# MirOculousShieldv2.net
KiCad netlist of a schematic drawn in EAGLE
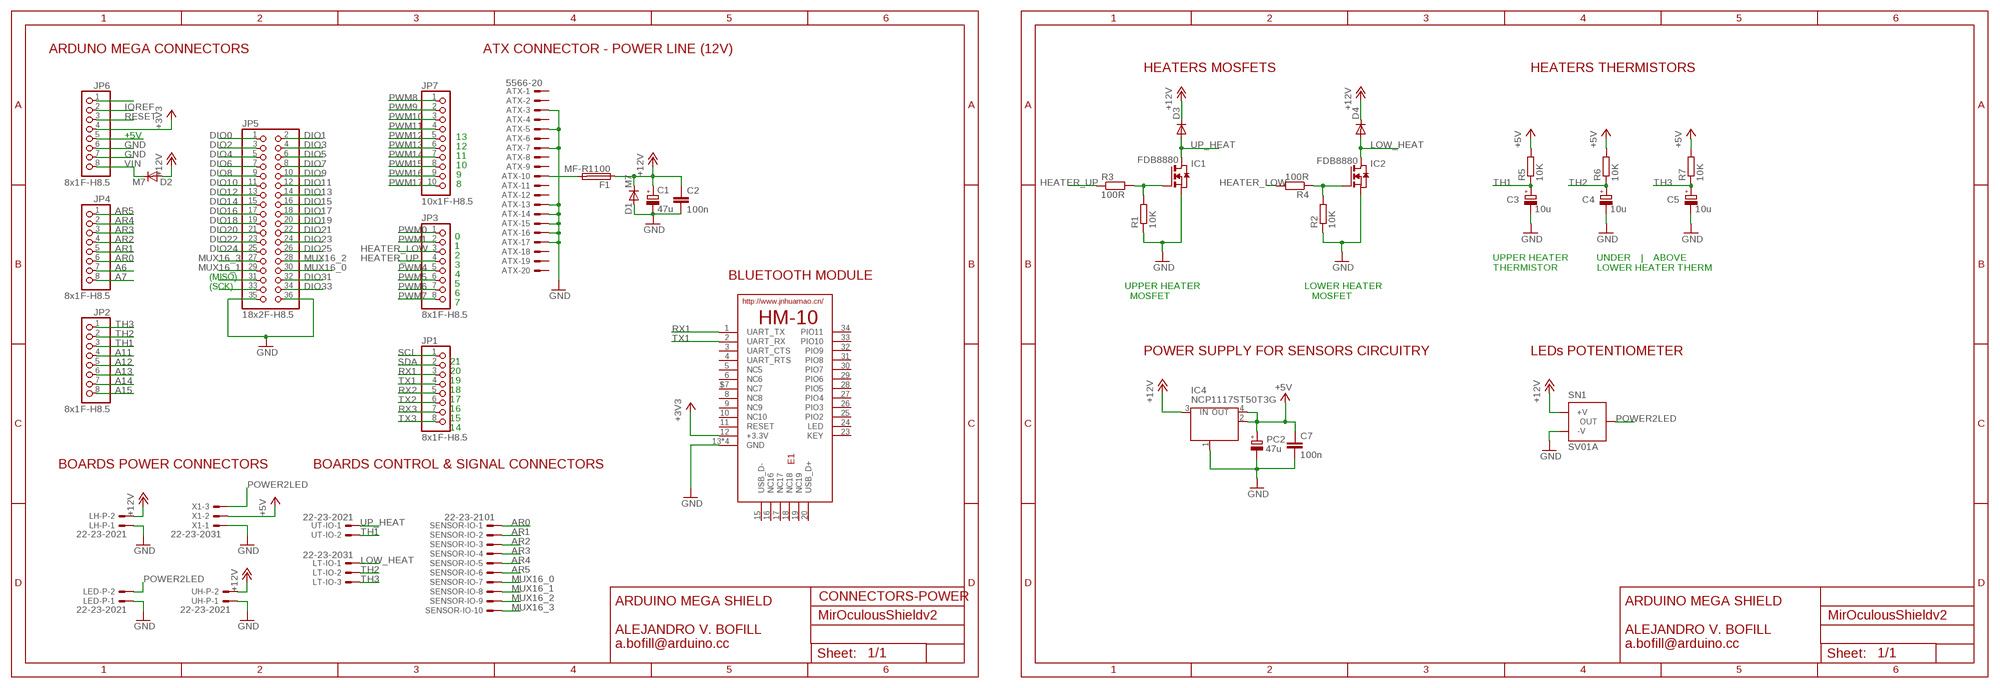
[diagram p0: schematic, sheet 1]

(export (version "E")
  (design (tool "Eeschema 10.0.6"))
  (components
    (comp (ref "ATX")
      (value "5566-20")
      (footprint "eagle-import:5566-20")
      (fields (field (name "OC_FARNELL") "9734252"))
      (libsource (lib "eagle-import") (part "5566-20"))
    )
    (comp (ref "C1")
      (value "47u")
      (footprint "eagle-import:PANASONIC_D")
      (libsource (lib "eagle-import") (part "CPOL-EUD"))
    )
    (comp (ref "C2")
      (value "100n")
      (footprint "eagle-import:C0603")
      (libsource (lib "eagle-import") (part "C-EUC0603"))
    )
    (comp (ref "C3")
      (value "10u")
      (footprint "eagle-import:A_3216-18R")
      (libsource (lib "eagle-import") (part "CPOL-EUA/3216-18R"))
    )
    (comp (ref "C4")
      (value "10u")
      (footprint "eagle-import:A_3216-18R")
      (libsource (lib "eagle-import") (part "CPOL-EUA/3216-18R"))
    )
    (comp (ref "C5")
      (value "10u")
      (footprint "eagle-import:A_3216-18R")
      (libsource (lib "eagle-import") (part "CPOL-EUA/3216-18R"))
    )
    (comp (ref "C7")
      (value "100n")
      (footprint "eagle-import:C0603")
      (libsource (lib "eagle-import") (part "C-EUC0603"))
    )
    (comp (ref "D1")
      (value "M7")
      (footprint "eagle-import:SMB")
      (libsource (lib "eagle-import") (part "DIODE-SMB"))
    )
    (comp (ref "D2")
      (value "M7")
      (footprint "eagle-import:SMB")
      (libsource (lib "eagle-import") (part "DIODE-SMB"))
    )
    (comp (ref "D3")
      (value "RGL34A")
      (footprint "eagle-import:DO-213AA_DIODE")
      (libsource (lib "eagle-import") (part "DO-213_DIODE"))
    )
    (comp (ref "D4")
      (value "RGL34A")
      (footprint "eagle-import:DO-213AA_DIODE")
      (libsource (lib "eagle-import") (part "DO-213_DIODE"))
    )
    (comp (ref "E1")
      (value "HM-10-BOARD")
      (footprint "eagle-import:26.9X13X2.2_BOARD")
      (libsource (lib "eagle-import") (part "HM-10-BOARD"))
    )
    (comp (ref "F1")
      (value "MF-R1100")
      (footprint "eagle-import:LITTLEFUSE")
      (libsource (lib "eagle-import") (part "LITTLEFUSE"))
    )
    (comp (ref "IC1")
      (value "FDB8880")
      (footprint "eagle-import:FDB8880")
      (libsource (lib "eagle-import") (part "FDB8880"))
    )
    (comp (ref "IC2")
      (value "FDB8880")
      (footprint "eagle-import:FDB8880")
      (libsource (lib "eagle-import") (part "FDB8880"))
    )
    (comp (ref "IC4")
      (value "NCP1117ST50T3G")
      (footprint "eagle-import:SOT223")
      (libsource (lib "eagle-import") (part "MC33269ST-3.3T3"))
    )
    (comp (ref "JP1")
      (value "8x1F-H8.5")
      (footprint "eagle-import:1X08")
      (libsource (lib "eagle-import") (part "PINHD-1X8"))
    )
    (comp (ref "JP2")
      (value "8x1F-H8.5")
      (footprint "eagle-import:1X08")
      (libsource (lib "eagle-import") (part "PINHD-1X8"))
    )
    (comp (ref "JP3")
      (value "8x1F-H8.5")
      (footprint "eagle-import:1X08")
      (libsource (lib "eagle-import") (part "PINHD-1X8"))
    )
    (comp (ref "JP4")
      (value "8x1F-H8.5")
      (footprint "eagle-import:1X08")
      (libsource (lib "eagle-import") (part "PINHD-1X8"))
    )
    (comp (ref "JP5")
      (value "18x2F-H8.5")
      (footprint "eagle-import:2X18")
      (libsource (lib "eagle-import") (part "PINHD-2X18"))
    )
    (comp (ref "JP6")
      (value "8x1F-H8.5")
      (footprint "eagle-import:1X08")
      (libsource (lib "eagle-import") (part "PINHD-1X8"))
    )
    (comp (ref "JP7")
      (value "10x1F-H8.5")
      (footprint "eagle-import:1X10")
      (libsource (lib "eagle-import") (part "PINHD-1X10_ARD"))
    )
    (comp (ref "LED-P")
      (value "22-23-2021")
      (footprint "eagle-import:22-23-2021")
      (fields (field (name "MF") "MOLEX"))
      (libsource (lib "eagle-import") (part "22-23-2021"))
    )
    (comp (ref "LH-P")
      (value "22-23-2021")
      (footprint "eagle-import:22-23-2021")
      (fields (field (name "MF") "MOLEX"))
      (libsource (lib "eagle-import") (part "22-23-2021"))
    )
    (comp (ref "LT-IO")
      (value "22-23-2031")
      (footprint "eagle-import:22-23-2031")
      (fields (field (name "MF") "MOLEX"))
      (libsource (lib "eagle-import") (part "22-23-2031"))
    )
    (comp (ref "PC2")
      (value "47u")
      (footprint "eagle-import:PANASONIC_D")
      (libsource (lib "eagle-import") (part "CPOL-EUD"))
    )
    (comp (ref "R1")
      (value "10K")
      (footprint "eagle-import:R0603")
      (libsource (lib "eagle-import") (part "R-EU_R0603"))
    )
    (comp (ref "R2")
      (value "10K")
      (footprint "eagle-import:R0603")
      (libsource (lib "eagle-import") (part "R-EU_R0603"))
    )
    (comp (ref "R3")
      (value "100R")
      (footprint "eagle-import:R0603")
      (libsource (lib "eagle-import") (part "R-EU_R0603"))
    )
    (comp (ref "R4")
      (value "100R")
      (footprint "eagle-import:R0603")
      (libsource (lib "eagle-import") (part "R-EU_R0603"))
    )
    (comp (ref "R5")
      (value "10K")
      (footprint "eagle-import:R0603")
      (libsource (lib "eagle-import") (part "R-EU_R0603"))
    )
    (comp (ref "R6")
      (value "10K")
      (footprint "eagle-import:R0603")
      (libsource (lib "eagle-import") (part "R-EU_R0603"))
    )
    (comp (ref "R7")
      (value "10K")
      (footprint "eagle-import:R0603")
      (libsource (lib "eagle-import") (part "R-EU_R0603"))
    )
    (comp (ref "SENSOR-IO")
      (value "22-23-2101")
      (footprint "eagle-import:22-23-2101")
      (fields (field (name "MF") "MOLEX"))
      (libsource (lib "eagle-import") (part "22-23-2101"))
    )
    (comp (ref "SN1")
      (value "SV01A")
      (footprint "eagle-import:SV01A")
      (libsource (lib "eagle-import") (part "SV01A"))
    )
    (comp (ref "UH-P")
      (value "22-23-2021")
      (footprint "eagle-import:22-23-2021")
      (fields (field (name "MF") "MOLEX"))
      (libsource (lib "eagle-import") (part "22-23-2021"))
    )
    (comp (ref "UT-IO")
      (value "22-23-2021")
      (footprint "eagle-import:22-23-2021")
      (fields (field (name "MF") "MOLEX"))
      (libsource (lib "eagle-import") (part "22-23-2021"))
    )
    (comp (ref "X1")
      (value "22-23-2031")
      (footprint "eagle-import:22-23-2031")
      (fields (field (name "MF") "MOLEX"))
      (libsource (lib "eagle-import") (part "22-23-2031"))
    )
  )
  (nets
    (net (code "1") (name "+3V3") (class "Default")
      (node (ref "E1") (pin "12") (pinfunction "+3.3V_12") (pintype "bidirectional"))
      (node (ref "JP6") (pin "4") (pinfunction "4_4") (pintype "passive"))
    )
    (net (code "2") (name "+5V") (class "Default")
      (node (ref "C7") (pin "1") (pinfunction "1_1") (pintype "passive"))
      (node (ref "IC4") (pin "2") (pinfunction "OUT_2") (pintype "passive"))
      (node (ref "IC4") (pin "4") (pinfunction "OUT_4") (pintype "passive"))
      (node (ref "PC2") (pin "+") (pinfunction "+_+") (pintype "passive"))
      (node (ref "R5") (pin "2") (pinfunction "2_2") (pintype "passive"))
      (node (ref "R6") (pin "2") (pinfunction "2_2") (pintype "passive"))
      (node (ref "R7") (pin "2") (pinfunction "2_2") (pintype "passive"))
      (node (ref "X1") (pin "2") (pinfunction "S_2") (pintype "passive"))
    )
    (net (code "3") (name "+12V") (class "Default")
      (node (ref "C1") (pin "+") (pinfunction "+_+") (pintype "passive"))
      (node (ref "C2") (pin "1") (pinfunction "1_1") (pintype "passive"))
      (node (ref "D1") (pin "C") (pinfunction "C_C") (pintype "passive"))
      (node (ref "D2") (pin "A") (pinfunction "A_A") (pintype "passive"))
      (node (ref "D3") (pin "P$2") (pinfunction "C_P$2") (pintype "passive"))
      (node (ref "D4") (pin "P$2") (pinfunction "C_P$2") (pintype "passive"))
      (node (ref "F1") (pin "1") (pinfunction "1_1") (pintype "passive"))
      (node (ref "IC4") (pin "3") (pinfunction "IN_3") (pintype "input"))
      (node (ref "LH-P") (pin "2") (pinfunction "S_2") (pintype "passive"))
      (node (ref "SN1") (pin "3") (pinfunction "+V_3") (pintype "passive"))
      (node (ref "UH-P") (pin "2") (pinfunction "S_2") (pintype "passive"))
    )
    (net (code "4") (name "/A6") (class "Default")
      (node (ref "JP4") (pin "7") (pinfunction "7_7") (pintype "passive"))
    )
    (net (code "5") (name "/A7") (class "Default")
      (node (ref "JP4") (pin "8") (pinfunction "8_8") (pintype "passive"))
    )
    (net (code "6") (name "/A11") (class "Default")
      (node (ref "JP2") (pin "4") (pinfunction "4_4") (pintype "passive"))
    )
    (net (code "7") (name "/A12") (class "Default")
      (node (ref "JP2") (pin "5") (pinfunction "5_5") (pintype "passive"))
    )
    (net (code "8") (name "/A13") (class "Default")
      (node (ref "JP2") (pin "6") (pinfunction "6_6") (pintype "passive"))
    )
    (net (code "9") (name "/A14") (class "Default")
      (node (ref "JP2") (pin "7") (pinfunction "7_7") (pintype "passive"))
    )
    (net (code "10") (name "/A15") (class "Default")
      (node (ref "JP2") (pin "8") (pinfunction "8_8") (pintype "passive"))
    )
    (net (code "11") (name "/AR0") (class "Default")
      (node (ref "JP4") (pin "6") (pinfunction "6_6") (pintype "passive"))
      (node (ref "SENSOR-IO") (pin "1") (pinfunction "S_1") (pintype "passive"))
    )
    (net (code "12") (name "/AR1") (class "Default")
      (node (ref "JP4") (pin "5") (pinfunction "5_5") (pintype "passive"))
      (node (ref "SENSOR-IO") (pin "2") (pinfunction "S_2") (pintype "passive"))
    )
    (net (code "13") (name "/AR2") (class "Default")
      (node (ref "JP4") (pin "4") (pinfunction "4_4") (pintype "passive"))
      (node (ref "SENSOR-IO") (pin "3") (pinfunction "S_3") (pintype "passive"))
    )
    (net (code "14") (name "/AR3") (class "Default")
      (node (ref "JP4") (pin "3") (pinfunction "3_3") (pintype "passive"))
      (node (ref "SENSOR-IO") (pin "4") (pinfunction "S_4") (pintype "passive"))
    )
    (net (code "15") (name "/AR4") (class "Default")
      (node (ref "JP4") (pin "2") (pinfunction "2_2") (pintype "passive"))
      (node (ref "SENSOR-IO") (pin "5") (pinfunction "S_5") (pintype "passive"))
    )
    (net (code "16") (name "/AR5") (class "Default")
      (node (ref "JP4") (pin "1") (pinfunction "1_1") (pintype "passive"))
      (node (ref "SENSOR-IO") (pin "6") (pinfunction "S_6") (pintype "passive"))
    )
    (net (code "17") (name "/DIO0") (class "Default")
      (node (ref "JP5") (pin "1") (pinfunction "1_1") (pintype "passive"))
    )
    (net (code "18") (name "/DIO1") (class "Default")
      (node (ref "JP5") (pin "2") (pinfunction "2_2") (pintype "passive"))
    )
    (net (code "19") (name "/DIO2") (class "Default")
      (node (ref "JP5") (pin "3") (pinfunction "3_3") (pintype "passive"))
    )
    (net (code "20") (name "/DIO3") (class "Default")
      (node (ref "JP5") (pin "4") (pinfunction "4_4") (pintype "passive"))
    )
    (net (code "21") (name "/DIO4") (class "Default")
      (node (ref "JP5") (pin "5") (pinfunction "5_5") (pintype "passive"))
    )
    (net (code "22") (name "/DIO5") (class "Default")
      (node (ref "JP5") (pin "6") (pinfunction "6_6") (pintype "passive"))
    )
    (net (code "23") (name "/DIO6") (class "Default")
      (node (ref "JP5") (pin "7") (pinfunction "7_7") (pintype "passive"))
    )
    (net (code "24") (name "/DIO7") (class "Default")
      (node (ref "JP5") (pin "8") (pinfunction "8_8") (pintype "passive"))
    )
    (net (code "25") (name "/DIO8") (class "Default")
      (node (ref "JP5") (pin "9") (pinfunction "9_9") (pintype "passive"))
    )
    (net (code "26") (name "/DIO9") (class "Default")
      (node (ref "JP5") (pin "10") (pinfunction "10_10") (pintype "passive"))
    )
    (net (code "27") (name "/DIO10") (class "Default")
      (node (ref "JP5") (pin "11") (pinfunction "11_11") (pintype "passive"))
    )
    (net (code "28") (name "/DIO11") (class "Default")
      (node (ref "JP5") (pin "12") (pinfunction "12_12") (pintype "passive"))
    )
    (net (code "29") (name "/DIO12") (class "Default")
      (node (ref "JP5") (pin "13") (pinfunction "13_13") (pintype "passive"))
    )
    (net (code "30") (name "/DIO13") (class "Default")
      (node (ref "JP5") (pin "14") (pinfunction "14_14") (pintype "passive"))
    )
    (net (code "31") (name "/DIO14") (class "Default")
      (node (ref "JP5") (pin "15") (pinfunction "15_15") (pintype "passive"))
    )
    (net (code "32") (name "/DIO15") (class "Default")
      (node (ref "JP5") (pin "16") (pinfunction "16_16") (pintype "passive"))
    )
    (net (code "33") (name "/DIO16") (class "Default")
      (node (ref "JP5") (pin "17") (pinfunction "17_17") (pintype "passive"))
    )
    (net (code "34") (name "/DIO17") (class "Default")
      (node (ref "JP5") (pin "18") (pinfunction "18_18") (pintype "passive"))
    )
    (net (code "35") (name "/DIO18") (class "Default")
      (node (ref "JP5") (pin "19") (pinfunction "19_19") (pintype "passive"))
    )
    (net (code "36") (name "/DIO19") (class "Default")
      (node (ref "JP5") (pin "20") (pinfunction "20_20") (pintype "passive"))
    )
    (net (code "37") (name "/DIO20") (class "Default")
      (node (ref "JP5") (pin "21") (pinfunction "21_21") (pintype "passive"))
    )
    (net (code "38") (name "/DIO21") (class "Default")
      (node (ref "JP5") (pin "22") (pinfunction "22_22") (pintype "passive"))
    )
    (net (code "39") (name "/DIO22") (class "Default")
      (node (ref "JP5") (pin "23") (pinfunction "23_23") (pintype "passive"))
    )
    (net (code "40") (name "/DIO23") (class "Default")
      (node (ref "JP5") (pin "24") (pinfunction "24_24") (pintype "passive"))
    )
    (net (code "41") (name "/DIO24") (class "Default")
      (node (ref "JP5") (pin "25") (pinfunction "25_25") (pintype "passive"))
    )
    (net (code "42") (name "/DIO25") (class "Default")
      (node (ref "JP5") (pin "26") (pinfunction "26_26") (pintype "passive"))
    )
    (net (code "43") (name "/DIO31") (class "Default")
      (node (ref "JP5") (pin "32") (pinfunction "32_32") (pintype "passive"))
    )
    (net (code "44") (name "/DIO33") (class "Default")
      (node (ref "JP5") (pin "34") (pinfunction "34_34") (pintype "passive"))
    )
    (net (code "45") (name "/HEATER_LOW") (class "Default")
      (node (ref "JP3") (pin "3") (pinfunction "3_3") (pintype "passive"))
      (node (ref "R4") (pin "2") (pinfunction "2_2") (pintype "passive"))
    )
    (net (code "46") (name "/HEATER_UP") (class "Default")
      (node (ref "JP3") (pin "4") (pinfunction "4_4") (pintype "passive"))
      (node (ref "R3") (pin "1") (pinfunction "1_1") (pintype "passive"))
    )
    (net (code "47") (name "/IOREF") (class "Default")
      (node (ref "JP6") (pin "2") (pinfunction "2_2") (pintype "passive"))
    )
    (net (code "48") (name "/LOW_HEAT") (class "Default")
      (node (ref "D4") (pin "P$1") (pinfunction "A_P$1") (pintype "passive"))
      (node (ref "IC2") (pin "2") (pinfunction "D_2") (pintype "passive"))
      (node (ref "LT-IO") (pin "1") (pinfunction "S_1") (pintype "passive"))
    )
    (net (code "49") (name "/MUX16_0") (class "Default")
      (node (ref "JP5") (pin "30") (pinfunction "30_30") (pintype "passive"))
      (node (ref "SENSOR-IO") (pin "7") (pinfunction "S_7") (pintype "passive"))
    )
    (net (code "50") (name "/MUX16_1") (class "Default")
      (node (ref "JP5") (pin "29") (pinfunction "29_29") (pintype "passive"))
      (node (ref "SENSOR-IO") (pin "8") (pinfunction "S_8") (pintype "passive"))
    )
    (net (code "51") (name "/MUX16_2") (class "Default")
      (node (ref "JP5") (pin "28") (pinfunction "28_28") (pintype "passive"))
      (node (ref "SENSOR-IO") (pin "9") (pinfunction "S_9") (pintype "passive"))
    )
    (net (code "52") (name "/MUX16_3") (class "Default")
      (node (ref "JP5") (pin "27") (pinfunction "27_27") (pintype "passive"))
      (node (ref "SENSOR-IO") (pin "10") (pinfunction "S_10") (pintype "passive"))
    )
    (net (code "53") (name "/POWER2LED") (class "Default")
      (node (ref "LED-P") (pin "2") (pinfunction "S_2") (pintype "passive"))
      (node (ref "SN1") (pin "2") (pinfunction "OUT_2") (pintype "passive"))
      (node (ref "X1") (pin "3") (pinfunction "S_3") (pintype "passive"))
    )
    (net (code "54") (name "/PWM0") (class "Default")
      (node (ref "JP3") (pin "1") (pinfunction "1_1") (pintype "passive"))
    )
    (net (code "55") (name "/PWM1") (class "Default")
      (node (ref "JP3") (pin "2") (pinfunction "2_2") (pintype "passive"))
    )
    (net (code "56") (name "/PWM4") (class "Default")
      (node (ref "JP3") (pin "5") (pinfunction "5_5") (pintype "passive"))
    )
    (net (code "57") (name "/PWM5") (class "Default")
      (node (ref "JP3") (pin "6") (pinfunction "6_6") (pintype "passive"))
    )
    (net (code "58") (name "/PWM6") (class "Default")
      (node (ref "JP3") (pin "7") (pinfunction "7_7") (pintype "passive"))
    )
    (net (code "59") (name "/PWM7") (class "Default")
      (node (ref "JP3") (pin "8") (pinfunction "8_8") (pintype "passive"))
    )
    (net (code "60") (name "/PWM8") (class "Default")
      (node (ref "JP7") (pin "1") (pinfunction "1_1") (pintype "passive"))
    )
    (net (code "61") (name "/PWM9") (class "Default")
      (node (ref "JP7") (pin "2") (pinfunction "2_2") (pintype "passive"))
    )
    (net (code "62") (name "/PWM10") (class "Default")
      (node (ref "JP7") (pin "3") (pinfunction "3_3") (pintype "passive"))
    )
    (net (code "63") (name "/PWM11") (class "Default")
      (node (ref "JP7") (pin "4") (pinfunction "4_4") (pintype "passive"))
    )
    (net (code "64") (name "/PWM12") (class "Default")
      (node (ref "JP7") (pin "5") (pinfunction "5_5") (pintype "passive"))
    )
    (net (code "65") (name "/PWM13") (class "Default")
      (node (ref "JP7") (pin "6") (pinfunction "6_6") (pintype "passive"))
    )
    (net (code "66") (name "/PWM14") (class "Default")
      (node (ref "JP7") (pin "7") (pinfunction "7_7") (pintype "passive"))
    )
    (net (code "67") (name "/PWM15") (class "Default")
      (node (ref "JP7") (pin "8") (pinfunction "8_8") (pintype "passive"))
    )
    (net (code "68") (name "/PWM16") (class "Default")
      (node (ref "JP7") (pin "9") (pinfunction "9_9") (pintype "passive"))
    )
    (net (code "69") (name "/PWM17") (class "Default")
      (node (ref "JP7") (pin "10") (pinfunction "10_10") (pintype "passive"))
    )
    (net (code "70") (name "/RESET") (class "Default")
      (node (ref "JP6") (pin "3") (pinfunction "3_3") (pintype "passive"))
    )
    (net (code "71") (name "/RX1") (class "Default")
      (node (ref "E1") (pin "1") (pinfunction "UART_TX_1") (pintype "bidirectional"))
      (node (ref "JP1") (pin "3") (pinfunction "3_3") (pintype "passive"))
    )
    (net (code "72") (name "/RX2") (class "Default")
      (node (ref "JP1") (pin "5") (pinfunction "5_5") (pintype "passive"))
    )
    (net (code "73") (name "/RX3") (class "Default")
      (node (ref "JP1") (pin "7") (pinfunction "7_7") (pintype "passive"))
    )
    (net (code "74") (name "/SCL") (class "Default")
      (node (ref "JP1") (pin "1") (pinfunction "1_1") (pintype "passive"))
    )
    (net (code "75") (name "/SDA") (class "Default")
      (node (ref "JP1") (pin "2") (pinfunction "2_2") (pintype "passive"))
    )
    (net (code "76") (name "/TH1") (class "Default")
      (node (ref "C3") (pin "+") (pinfunction "+_+") (pintype "passive"))
      (node (ref "JP2") (pin "3") (pinfunction "3_3") (pintype "passive"))
      (node (ref "R5") (pin "1") (pinfunction "1_1") (pintype "passive"))
      (node (ref "UT-IO") (pin "2") (pinfunction "S_2") (pintype "passive"))
    )
    (net (code "77") (name "/TH2") (class "Default")
      (node (ref "C4") (pin "+") (pinfunction "+_+") (pintype "passive"))
      (node (ref "JP2") (pin "2") (pinfunction "2_2") (pintype "passive"))
      (node (ref "LT-IO") (pin "2") (pinfunction "S_2") (pintype "passive"))
      (node (ref "R6") (pin "1") (pinfunction "1_1") (pintype "passive"))
    )
    (net (code "78") (name "/TH3") (class "Default")
      (node (ref "C5") (pin "+") (pinfunction "+_+") (pintype "passive"))
      (node (ref "JP2") (pin "1") (pinfunction "1_1") (pintype "passive"))
      (node (ref "LT-IO") (pin "3") (pinfunction "S_3") (pintype "passive"))
      (node (ref "R7") (pin "1") (pinfunction "1_1") (pintype "passive"))
    )
    (net (code "79") (name "/TX1") (class "Default")
      (node (ref "E1") (pin "2") (pinfunction "UART_RX_2") (pintype "bidirectional"))
      (node (ref "JP1") (pin "4") (pinfunction "4_4") (pintype "passive"))
    )
    (net (code "80") (name "/TX2") (class "Default")
      (node (ref "JP1") (pin "6") (pinfunction "6_6") (pintype "passive"))
    )
    (net (code "81") (name "/TX3") (class "Default")
      (node (ref "JP1") (pin "8") (pinfunction "8_8") (pintype "passive"))
    )
    (net (code "82") (name "/UP_HEAT") (class "Default")
      (node (ref "D3") (pin "P$1") (pinfunction "A_P$1") (pintype "passive"))
      (node (ref "IC1") (pin "2") (pinfunction "D_2") (pintype "passive"))
      (node (ref "UT-IO") (pin "1") (pinfunction "S_1") (pintype "passive"))
    )
    (net (code "83") (name "/VIN") (class "Default")
      (node (ref "D2") (pin "C") (pinfunction "C_C") (pintype "passive"))
      (node (ref "JP6") (pin "8") (pinfunction "8_8") (pintype "passive"))
    )
    (net (code "84") (name "GND") (class "Default")
      (node (ref "ATX") (pin "13") (pinfunction "S_13") (pintype "passive"))
      (node (ref "ATX") (pin "14") (pinfunction "S_14") (pintype "passive"))
      (node (ref "ATX") (pin "15") (pinfunction "S_15") (pintype "passive"))
      (node (ref "ATX") (pin "16") (pinfunction "S_16") (pintype "passive"))
      (node (ref "ATX") (pin "17") (pinfunction "S_17") (pintype "passive"))
      (node (ref "ATX") (pin "3") (pinfunction "S_3") (pintype "passive"))
      (node (ref "ATX") (pin "5") (pinfunction "S_5") (pintype "passive"))
      (node (ref "ATX") (pin "7") (pinfunction "S_7") (pintype "passive"))
      (node (ref "C1") (pin "-") (pinfunction "-_-") (pintype "passive"))
      (node (ref "C2") (pin "2") (pinfunction "2_2") (pintype "passive"))
      (node (ref "C3") (pin "-") (pinfunction "-_-") (pintype "passive"))
      (node (ref "C4") (pin "-") (pinfunction "-_-") (pintype "passive"))
      (node (ref "C5") (pin "-") (pinfunction "-_-") (pintype "passive"))
      (node (ref "C7") (pin "2") (pinfunction "2_2") (pintype "passive"))
      (node (ref "D1") (pin "A") (pinfunction "A_A") (pintype "passive"))
      (node (ref "E1") (pin "13") (pinfunction "GND_13") (pintype "bidirectional"))
      (node (ref "E1") (pin "14") (pinfunction "GND_14") (pintype "bidirectional"))
      (node (ref "E1") (pin "21") (pinfunction "GND_21") (pintype "bidirectional"))
      (node (ref "E1") (pin "22") (pinfunction "GND_22") (pintype "bidirectional"))
      (node (ref "IC1") (pin "3") (pinfunction "S_3") (pintype "passive"))
      (node (ref "IC2") (pin "3") (pinfunction "S_3") (pintype "passive"))
      (node (ref "IC4") (pin "1") (pinfunction "GND/ADJ_1") (pintype "input"))
      (node (ref "JP5") (pin "35") (pinfunction "35_35") (pintype "passive"))
      (node (ref "JP5") (pin "36") (pinfunction "36_36") (pintype "passive"))
      (node (ref "JP6") (pin "6") (pinfunction "6_6") (pintype "passive"))
      (node (ref "JP6") (pin "7") (pinfunction "7_7") (pintype "passive"))
      (node (ref "LED-P") (pin "1") (pinfunction "S_1") (pintype "passive"))
      (node (ref "LH-P") (pin "1") (pinfunction "S_1") (pintype "passive"))
      (node (ref "PC2") (pin "-") (pinfunction "-_-") (pintype "passive"))
      (node (ref "R1") (pin "1") (pinfunction "1_1") (pintype "passive"))
      (node (ref "R2") (pin "1") (pinfunction "1_1") (pintype "passive"))
      (node (ref "SN1") (pin "1") (pinfunction "-V_1") (pintype "passive"))
      (node (ref "UH-P") (pin "1") (pinfunction "S_1") (pintype "passive"))
      (node (ref "X1") (pin "1") (pinfunction "S_1") (pintype "passive"))
    )
    (net (code "85") (name "Net-(ATXB-S)") (class "Default")
      (node (ref "ATX") (pin "10") (pinfunction "S_10") (pintype "passive"))
      (node (ref "F1") (pin "2") (pinfunction "2_2") (pintype "passive"))
    )
    (net (code "86") (name "Net-(IC1-G)") (class "Default")
      (node (ref "IC1") (pin "1") (pinfunction "G_1") (pintype "passive"))
      (node (ref "R1") (pin "2") (pinfunction "2_2") (pintype "passive"))
      (node (ref "R3") (pin "2") (pinfunction "2_2") (pintype "passive"))
    )
    (net (code "87") (name "Net-(IC2-G)") (class "Default")
      (node (ref "IC2") (pin "1") (pinfunction "G_1") (pintype "passive"))
      (node (ref "R2") (pin "2") (pinfunction "2_2") (pintype "passive"))
      (node (ref "R4") (pin "1") (pinfunction "1_1") (pintype "passive"))
    )
    (net (code "88") (name "unconnected-(ATXA-S-Pad1)") (class "Default")
      (node (ref "ATX") (pin "1") (pinfunction "S_1") (pintype "passive"))
    )
    (net (code "89") (name "unconnected-(ATXC-S-Pad11)") (class "Default")
      (node (ref "ATX") (pin "11") (pinfunction "S_11") (pintype "passive"))
    )
    (net (code "90") (name "unconnected-(ATXD-S-Pad12)") (class "Default")
      (node (ref "ATX") (pin "12") (pinfunction "S_12") (pintype "passive"))
    )
    (net (code "91") (name "unconnected-(ATXJ-S-Pad18)") (class "Default")
      (node (ref "ATX") (pin "18") (pinfunction "S_18") (pintype "passive"))
    )
    (net (code "92") (name "unconnected-(ATXK-S-Pad19)") (class "Default")
      (node (ref "ATX") (pin "19") (pinfunction "S_19") (pintype "passive"))
    )
    (net (code "93") (name "unconnected-(ATXL-S-Pad2)") (class "Default")
      (node (ref "ATX") (pin "2") (pinfunction "S_2") (pintype "passive"))
    )
    (net (code "94") (name "unconnected-(ATXM-S-Pad20)") (class "Default")
      (node (ref "ATX") (pin "20") (pinfunction "S_20") (pintype "passive"))
    )
    (net (code "95") (name "unconnected-(ATXO-S-Pad4)") (class "Default")
      (node (ref "ATX") (pin "4") (pinfunction "S_4") (pintype "passive"))
    )
    (net (code "96") (name "unconnected-(ATXQ-S-Pad6)") (class "Default")
      (node (ref "ATX") (pin "6") (pinfunction "S_6") (pintype "passive"))
    )
    (net (code "97") (name "unconnected-(ATXS-S-Pad8)") (class "Default")
      (node (ref "ATX") (pin "8") (pinfunction "S_8") (pintype "passive"))
    )
    (net (code "98") (name "unconnected-(ATXT-S-Pad9)") (class "Default")
      (node (ref "ATX") (pin "9") (pinfunction "S_9") (pintype "passive"))
    )
    (net (code "99") (name "unconnected-(E1-KEY-Pad23)") (class "Default")
      (node (ref "E1") (pin "23") (pinfunction "KEY_23") (pintype "bidirectional"))
    )
    (net (code "100") (name "unconnected-(E1-LED-Pad24)") (class "Default")
      (node (ref "E1") (pin "24") (pinfunction "LED_24") (pintype "bidirectional"))
    )
    (net (code "101") (name "unconnected-(E1-NC5-Pad5)") (class "Default")
      (node (ref "E1") (pin "5") (pinfunction "NC5_5") (pintype "bidirectional"))
    )
    (net (code "102") (name "unconnected-(E1-NC6-Pad6)") (class "Default")
      (node (ref "E1") (pin "6") (pinfunction "NC6_6") (pintype "bidirectional"))
    )
    (net (code "103") (name "unconnected-(E1-NC7-Pad$7)") (class "Default")
      (node (ref "E1") (pin "$7") (pinfunction "NC7_$7") (pintype "bidirectional"))
    )
    (net (code "104") (name "unconnected-(E1-NC8-Pad8)") (class "Default")
      (node (ref "E1") (pin "8") (pinfunction "NC8_8") (pintype "bidirectional"))
    )
    (net (code "105") (name "unconnected-(E1-NC9-Pad9)") (class "Default")
      (node (ref "E1") (pin "9") (pinfunction "NC9_9") (pintype "bidirectional"))
    )
    (net (code "106") (name "unconnected-(E1-NC10-Pad10)") (class "Default")
      (node (ref "E1") (pin "10") (pinfunction "NC10_10") (pintype "bidirectional"))
    )
    (net (code "107") (name "unconnected-(E1-NC16-Pad16)") (class "Default")
      (node (ref "E1") (pin "16") (pinfunction "NC16_16") (pintype "bidirectional"))
    )
    (net (code "108") (name "unconnected-(E1-NC17-Pad17)") (class "Default")
      (node (ref "E1") (pin "17") (pinfunction "NC17_17") (pintype "bidirectional"))
    )
    (net (code "109") (name "unconnected-(E1-NC18-Pad18)") (class "Default")
      (node (ref "E1") (pin "18") (pinfunction "NC18_18") (pintype "bidirectional"))
    )
    (net (code "110") (name "unconnected-(E1-NC19-Pad19)") (class "Default")
      (node (ref "E1") (pin "19") (pinfunction "NC19_19") (pintype "bidirectional"))
    )
    (net (code "111") (name "unconnected-(E1-PIO2-Pad25)") (class "Default")
      (node (ref "E1") (pin "25") (pinfunction "PIO2_25") (pintype "bidirectional"))
    )
    (net (code "112") (name "unconnected-(E1-PIO3-Pad26)") (class "Default")
      (node (ref "E1") (pin "26") (pinfunction "PIO3_26") (pintype "bidirectional"))
    )
    (net (code "113") (name "unconnected-(E1-PIO4-Pad27)") (class "Default")
      (node (ref "E1") (pin "27") (pinfunction "PIO4_27") (pintype "bidirectional"))
    )
    (net (code "114") (name "unconnected-(E1-PIO5-Pad28)") (class "Default")
      (node (ref "E1") (pin "28") (pinfunction "PIO5_28") (pintype "bidirectional"))
    )
    (net (code "115") (name "unconnected-(E1-PIO6-Pad29)") (class "Default")
      (node (ref "E1") (pin "29") (pinfunction "PIO6_29") (pintype "bidirectional"))
    )
    (net (code "116") (name "unconnected-(E1-PIO7-Pad30)") (class "Default")
      (node (ref "E1") (pin "30") (pinfunction "PIO7_30") (pintype "bidirectional"))
    )
    (net (code "117") (name "unconnected-(E1-PIO8-Pad31)") (class "Default")
      (node (ref "E1") (pin "31") (pinfunction "PIO8_31") (pintype "bidirectional"))
    )
    (net (code "118") (name "unconnected-(E1-PIO9-Pad32)") (class "Default")
      (node (ref "E1") (pin "32") (pinfunction "PIO9_32") (pintype "bidirectional"))
    )
    (net (code "119") (name "unconnected-(E1-PIO10-Pad33)") (class "Default")
      (node (ref "E1") (pin "33") (pinfunction "PIO10_33") (pintype "bidirectional"))
    )
    (net (code "120") (name "unconnected-(E1-PIO11-Pad34)") (class "Default")
      (node (ref "E1") (pin "34") (pinfunction "PIO11_34") (pintype "bidirectional"))
    )
    (net (code "121") (name "unconnected-(E1-RESET-Pad11)") (class "Default")
      (node (ref "E1") (pin "11") (pinfunction "RESET_11") (pintype "bidirectional"))
    )
    (net (code "122") (name "unconnected-(E1-UART_CTS-Pad3)") (class "Default")
      (node (ref "E1") (pin "3") (pinfunction "UART_CTS_3") (pintype "bidirectional"))
    )
    (net (code "123") (name "unconnected-(E1-UART_RTS-Pad4)") (class "Default")
      (node (ref "E1") (pin "4") (pinfunction "UART_RTS_4") (pintype "bidirectional"))
    )
    (net (code "124") (name "unconnected-(E1-USB_D+-Pad20)") (class "Default")
      (node (ref "E1") (pin "20") (pinfunction "USB_D+_20") (pintype "bidirectional"))
    )
    (net (code "125") (name "unconnected-(E1-USB_D--Pad15)") (class "Default")
      (node (ref "E1") (pin "15") (pinfunction "USB_D-_15") (pintype "bidirectional"))
    )
    (net (code "126") (name "unconnected-(JP5-Pad31)") (class "Default")
      (node (ref "JP5") (pin "31") (pinfunction "31_31") (pintype "passive"))
    )
    (net (code "127") (name "unconnected-(JP5-Pad33)") (class "Default")
      (node (ref "JP5") (pin "33") (pinfunction "33_33") (pintype "passive"))
    )
    (net (code "128") (name "unconnected-(JP6-Pad1)") (class "Default")
      (node (ref "JP6") (pin "1") (pinfunction "1_1") (pintype "passive"))
    )
    (net (code "129") (name "unconnected-(JP6-Pad5)") (class "Default")
      (node (ref "JP6") (pin "5") (pinfunction "5_5") (pintype "passive"))
    )
  )
)
